# left_revision1_0.net
KiCad netlist of a schematic drawn in EAGLE
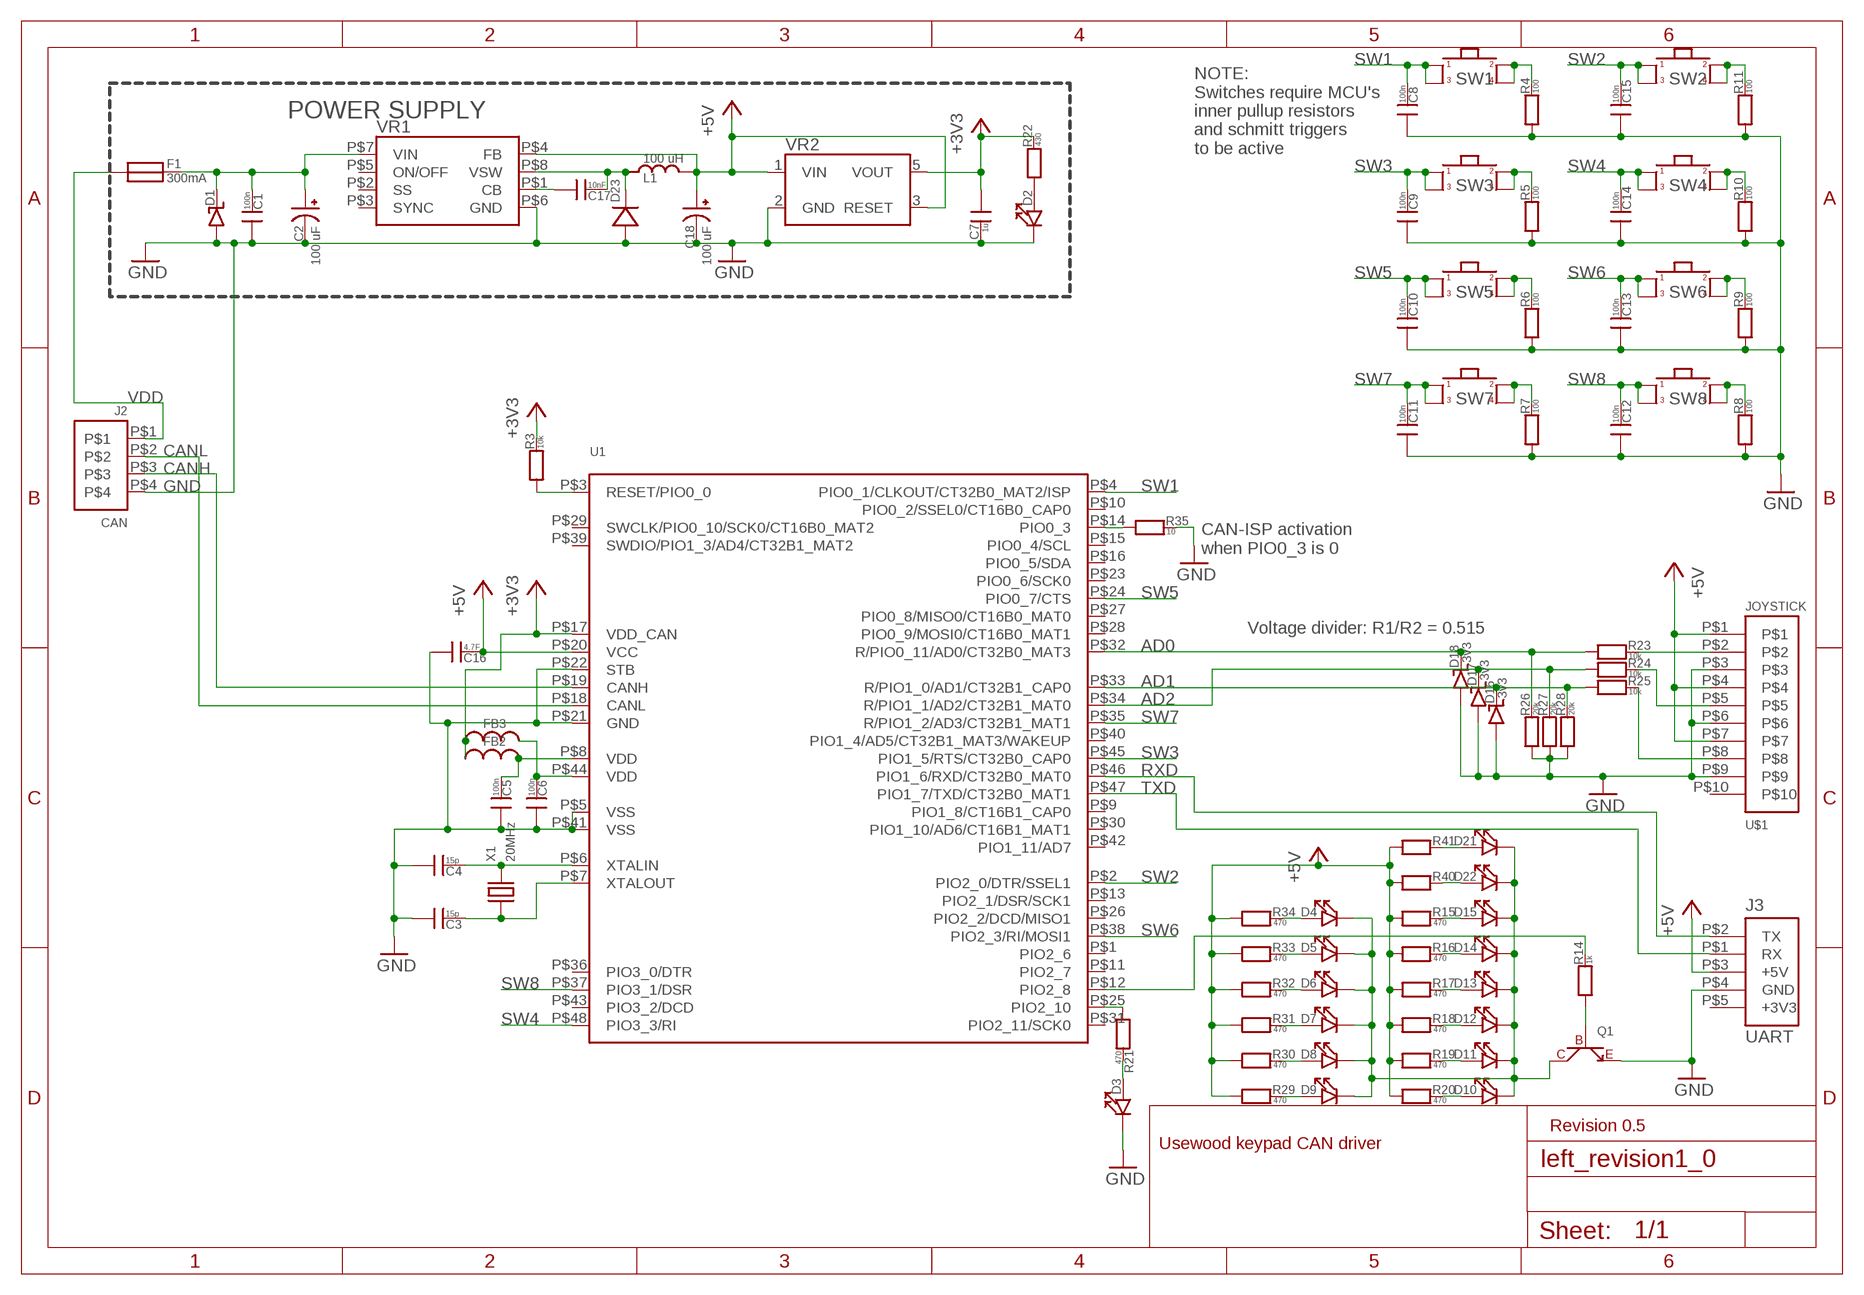
[diagram p0: schematic, sheet 1]

(export (version "E")
  (design (tool "Eeschema 10.0.6"))
  (components
    (comp (ref "C1")
      (value "100n")
      (footprint "eagle-import:0603_SILKSCREEN")
      (libsource (lib "eagle-import") (part "CAP0603_SILKSCREEN"))
    )
    (comp (ref "C2")
      (value "100 uF")
      (footprint "eagle-import:CAP_POL_SMD_10X10X10MM")
      (libsource (lib "eagle-import") (part "CAP_POLSMD_10X10X10MM"))
    )
    (comp (ref "C3")
      (value "15p")
      (footprint "eagle-import:0603_SILKSCREEN")
      (libsource (lib "eagle-import") (part "CAP0603_SILKSCREEN"))
    )
    (comp (ref "C4")
      (value "15p")
      (footprint "eagle-import:0603_SILKSCREEN")
      (libsource (lib "eagle-import") (part "CAP0603_SILKSCREEN"))
    )
    (comp (ref "C5")
      (value "100n")
      (footprint "eagle-import:0603_SILKSCREEN")
      (libsource (lib "eagle-import") (part "CAP0603_SILKSCREEN"))
    )
    (comp (ref "C6")
      (value "100n")
      (footprint "eagle-import:0603_SILKSCREEN")
      (libsource (lib "eagle-import") (part "CAP0603_SILKSCREEN"))
    )
    (comp (ref "C7")
      (value "1u")
      (footprint "eagle-import:0603_SILKSCREEN")
      (libsource (lib "eagle-import") (part "CAP0603_SILKSCREEN"))
    )
    (comp (ref "C8")
      (value "100n")
      (footprint "eagle-import:0603_SILKSCREEN")
      (libsource (lib "eagle-import") (part "CAP0603_SILKSCREEN"))
    )
    (comp (ref "C9")
      (value "100n")
      (footprint "eagle-import:0603_SILKSCREEN")
      (libsource (lib "eagle-import") (part "CAP0603_SILKSCREEN"))
    )
    (comp (ref "C10")
      (value "100n")
      (footprint "eagle-import:0603_SILKSCREEN")
      (libsource (lib "eagle-import") (part "CAP0603_SILKSCREEN"))
    )
    (comp (ref "C11")
      (value "100n")
      (footprint "eagle-import:0603_SILKSCREEN")
      (libsource (lib "eagle-import") (part "CAP0603_SILKSCREEN"))
    )
    (comp (ref "C12")
      (value "100n")
      (footprint "eagle-import:0603_SILKSCREEN")
      (libsource (lib "eagle-import") (part "CAP0603_SILKSCREEN"))
    )
    (comp (ref "C13")
      (value "100n")
      (footprint "eagle-import:0603_SILKSCREEN")
      (libsource (lib "eagle-import") (part "CAP0603_SILKSCREEN"))
    )
    (comp (ref "C14")
      (value "100n")
      (footprint "eagle-import:0603_SILKSCREEN")
      (libsource (lib "eagle-import") (part "CAP0603_SILKSCREEN"))
    )
    (comp (ref "C15")
      (value "100n")
      (footprint "eagle-import:0603_SILKSCREEN")
      (libsource (lib "eagle-import") (part "CAP0603_SILKSCREEN"))
    )
    (comp (ref "C16")
      (value "4.7F")
      (footprint "eagle-import:0603_SILKSCREEN")
      (libsource (lib "eagle-import") (part "CAP0603_SILKSCREEN"))
    )
    (comp (ref "C17")
      (value "10nF")
      (footprint "eagle-import:0603_SILKSCREEN")
      (libsource (lib "eagle-import") (part "CAP0603_SILKSCREEN"))
    )
    (comp (ref "C18")
      (value "100 uF")
      (footprint "eagle-import:CAP_POL_SMD_10X10X10MM")
      (libsource (lib "eagle-import") (part "CAP_POLSMD_10X10X10MM"))
    )
    (comp (ref "D1")
      (value "DIODE_TVSDO-214AA")
      (footprint "eagle-import:DO-214AB")
      (libsource (lib "eagle-import") (part "DIODE_TVSDO-214AA"))
    )
    (comp (ref "D2")
      (value "LED0603_SILKSCREEN")
      (footprint "eagle-import:0603_SILKSCREEN")
      (libsource (lib "eagle-import") (part "LED0603_SILKSCREEN"))
    )
    (comp (ref "D3")
      (value "LED0603_SILKSCREEN")
      (footprint "eagle-import:0603_SILKSCREEN")
      (libsource (lib "eagle-import") (part "LED0603_SILKSCREEN"))
    )
    (comp (ref "D4")
      (value "LED0603_SILKSCREEN")
      (footprint "eagle-import:0603_SILKSCREEN")
      (libsource (lib "eagle-import") (part "LED0603_SILKSCREEN"))
    )
    (comp (ref "D5")
      (value "LED0603_SILKSCREEN")
      (footprint "eagle-import:0603_SILKSCREEN")
      (libsource (lib "eagle-import") (part "LED0603_SILKSCREEN"))
    )
    (comp (ref "D6")
      (value "LED0603_SILKSCREEN")
      (footprint "eagle-import:0603_SILKSCREEN")
      (libsource (lib "eagle-import") (part "LED0603_SILKSCREEN"))
    )
    (comp (ref "D7")
      (value "LED0603_SILKSCREEN")
      (footprint "eagle-import:0603_SILKSCREEN")
      (libsource (lib "eagle-import") (part "LED0603_SILKSCREEN"))
    )
    (comp (ref "D8")
      (value "LED0603_SILKSCREEN")
      (footprint "eagle-import:0603_SILKSCREEN")
      (libsource (lib "eagle-import") (part "LED0603_SILKSCREEN"))
    )
    (comp (ref "D9")
      (value "LED0603_SILKSCREEN")
      (footprint "eagle-import:0603_SILKSCREEN")
      (libsource (lib "eagle-import") (part "LED0603_SILKSCREEN"))
    )
    (comp (ref "D10")
      (value "LED0603_SILKSCREEN")
      (footprint "eagle-import:0603_SILKSCREEN")
      (libsource (lib "eagle-import") (part "LED0603_SILKSCREEN"))
    )
    (comp (ref "D11")
      (value "LED0603_SILKSCREEN")
      (footprint "eagle-import:0603_SILKSCREEN")
      (libsource (lib "eagle-import") (part "LED0603_SILKSCREEN"))
    )
    (comp (ref "D12")
      (value "LED0603_SILKSCREEN")
      (footprint "eagle-import:0603_SILKSCREEN")
      (libsource (lib "eagle-import") (part "LED0603_SILKSCREEN"))
    )
    (comp (ref "D13")
      (value "LED0603_SILKSCREEN")
      (footprint "eagle-import:0603_SILKSCREEN")
      (libsource (lib "eagle-import") (part "LED0603_SILKSCREEN"))
    )
    (comp (ref "D14")
      (value "LED0603_SILKSCREEN")
      (footprint "eagle-import:0603_SILKSCREEN")
      (libsource (lib "eagle-import") (part "LED0603_SILKSCREEN"))
    )
    (comp (ref "D15")
      (value "LED0603_SILKSCREEN")
      (footprint "eagle-import:0603_SILKSCREEN")
      (libsource (lib "eagle-import") (part "LED0603_SILKSCREEN"))
    )
    (comp (ref "D16")
      (value "3v3")
      (footprint "eagle-import:SOD123")
      (libsource (lib "eagle-import") (part "DIODE_ZENERSDO123"))
    )
    (comp (ref "D17")
      (value "3v3")
      (footprint "eagle-import:SOD123")
      (libsource (lib "eagle-import") (part "DIODE_ZENERSDO123"))
    )
    (comp (ref "D18")
      (value "3v3")
      (footprint "eagle-import:SOD123")
      (libsource (lib "eagle-import") (part "DIODE_ZENERSDO123"))
    )
    (comp (ref "D21")
      (value "LED0603_SILKSCREEN")
      (footprint "eagle-import:0603_SILKSCREEN")
      (libsource (lib "eagle-import") (part "LED0603_SILKSCREEN"))
    )
    (comp (ref "D22")
      (value "LED0603_SILKSCREEN")
      (footprint "eagle-import:0603_SILKSCREEN")
      (libsource (lib "eagle-import") (part "LED0603_SILKSCREEN"))
    )
    (comp (ref "D23")
      (value "DIODEDO219AB")
      (footprint "eagle-import:DO219AB")
      (libsource (lib "eagle-import") (part "DIODEDO219AB"))
    )
    (comp (ref "F1")
      (value "300mA")
      (footprint "eagle-import:FUSE_100MA")
      (libsource (lib "eagle-import") (part "FUSE100MA"))
    )
    (comp (ref "FB2")
      (value "FERRITE0603_SILKSCREEN")
      (footprint "eagle-import:0603_SILKSCREEN")
      (libsource (lib "eagle-import") (part "FERRITE0603_SILKSCREEN"))
    )
    (comp (ref "FB3")
      (value "FERRITE0603_SILKSCREEN")
      (footprint "eagle-import:0603_SILKSCREEN")
      (libsource (lib "eagle-import") (part "FERRITE0603_SILKSCREEN"))
    )
    (comp (ref "J2")
      (value "CAN")
      (footprint "eagle-import:MOLEX_MICRO-FIT_4WAY")
      (libsource (lib "eagle-import") (part "MOLEX_MICRO-FIT_4WAYTH"))
    )
    (comp (ref "J3")
      (value "UART")
      (footprint "eagle-import:HEADER5_1")
      (libsource (lib "eagle-import") (part "HEADER_USARTTH"))
    )
    (comp (ref "L1")
      (value "100 uH")
      (footprint "eagle-import:INDUCTOR_BOURNS_10X13X5MM")
      (libsource (lib "eagle-import") (part "INDUCTORBOURNS_10X13X5MM"))
    )
    (comp (ref "Q1")
      (value "NPN_TRANSISTORSOT323")
      (footprint "eagle-import:SOT323")
      (libsource (lib "eagle-import") (part "NPN_TRANSISTORSOT323"))
    )
    (comp (ref "R3")
      (value "10k")
      (footprint "eagle-import:0603_SILKSCREEN")
      (libsource (lib "eagle-import") (part "RES0604_SILKSCREEN"))
    )
    (comp (ref "R4")
      (value "100")
      (footprint "eagle-import:0603_SILKSCREEN")
      (libsource (lib "eagle-import") (part "RES0604_SILKSCREEN"))
    )
    (comp (ref "R5")
      (value "100")
      (footprint "eagle-import:0603_SILKSCREEN")
      (libsource (lib "eagle-import") (part "RES0604_SILKSCREEN"))
    )
    (comp (ref "R6")
      (value "100")
      (footprint "eagle-import:0603_SILKSCREEN")
      (libsource (lib "eagle-import") (part "RES0604_SILKSCREEN"))
    )
    (comp (ref "R7")
      (value "100")
      (footprint "eagle-import:0603_SILKSCREEN")
      (libsource (lib "eagle-import") (part "RES0604_SILKSCREEN"))
    )
    (comp (ref "R8")
      (value "100")
      (footprint "eagle-import:0603_SILKSCREEN")
      (libsource (lib "eagle-import") (part "RES0604_SILKSCREEN"))
    )
    (comp (ref "R9")
      (value "100")
      (footprint "eagle-import:0603_SILKSCREEN")
      (libsource (lib "eagle-import") (part "RES0604_SILKSCREEN"))
    )
    (comp (ref "R10")
      (value "100")
      (footprint "eagle-import:0603_SILKSCREEN")
      (libsource (lib "eagle-import") (part "RES0604_SILKSCREEN"))
    )
    (comp (ref "R11")
      (value "100")
      (footprint "eagle-import:0603_SILKSCREEN")
      (libsource (lib "eagle-import") (part "RES0604_SILKSCREEN"))
    )
    (comp (ref "R14")
      (value "1k")
      (footprint "eagle-import:0603_SILKSCREEN")
      (libsource (lib "eagle-import") (part "RES0604_SILKSCREEN"))
    )
    (comp (ref "R15")
      (value "470")
      (footprint "eagle-import:0603_SILKSCREEN")
      (libsource (lib "eagle-import") (part "RES0604_SILKSCREEN"))
    )
    (comp (ref "R16")
      (value "470")
      (footprint "eagle-import:0603_SILKSCREEN")
      (libsource (lib "eagle-import") (part "RES0604_SILKSCREEN"))
    )
    (comp (ref "R17")
      (value "470")
      (footprint "eagle-import:0603_SILKSCREEN")
      (libsource (lib "eagle-import") (part "RES0604_SILKSCREEN"))
    )
    (comp (ref "R18")
      (value "470")
      (footprint "eagle-import:0603_SILKSCREEN")
      (libsource (lib "eagle-import") (part "RES0604_SILKSCREEN"))
    )
    (comp (ref "R19")
      (value "470")
      (footprint "eagle-import:0603_SILKSCREEN")
      (libsource (lib "eagle-import") (part "RES0604_SILKSCREEN"))
    )
    (comp (ref "R20")
      (value "470")
      (footprint "eagle-import:0603_SILKSCREEN")
      (libsource (lib "eagle-import") (part "RES0604_SILKSCREEN"))
    )
    (comp (ref "R21")
      (value "470")
      (footprint "eagle-import:0603_SILKSCREEN")
      (libsource (lib "eagle-import") (part "RES0604_SILKSCREEN"))
    )
    (comp (ref "R22")
      (value "430")
      (footprint "eagle-import:0603_SILKSCREEN")
      (libsource (lib "eagle-import") (part "RES0604_SILKSCREEN"))
    )
    (comp (ref "R23")
      (value "10k")
      (footprint "eagle-import:0603_SILKSCREEN")
      (libsource (lib "eagle-import") (part "RES0604_SILKSCREEN"))
    )
    (comp (ref "R24")
      (value "10k")
      (footprint "eagle-import:0603_SILKSCREEN")
      (libsource (lib "eagle-import") (part "RES0604_SILKSCREEN"))
    )
    (comp (ref "R25")
      (value "10k")
      (footprint "eagle-import:0603_SILKSCREEN")
      (libsource (lib "eagle-import") (part "RES0604_SILKSCREEN"))
    )
    (comp (ref "R26")
      (value "20k")
      (footprint "eagle-import:0603_SILKSCREEN")
      (libsource (lib "eagle-import") (part "RES0604_SILKSCREEN"))
    )
    (comp (ref "R27")
      (value "20k")
      (footprint "eagle-import:0603_SILKSCREEN")
      (libsource (lib "eagle-import") (part "RES0604_SILKSCREEN"))
    )
    (comp (ref "R28")
      (value "20k")
      (footprint "eagle-import:0603_SILKSCREEN")
      (libsource (lib "eagle-import") (part "RES0604_SILKSCREEN"))
    )
    (comp (ref "R29")
      (value "470")
      (footprint "eagle-import:0603_SILKSCREEN")
      (libsource (lib "eagle-import") (part "RES0604_SILKSCREEN"))
    )
    (comp (ref "R30")
      (value "470")
      (footprint "eagle-import:0603_SILKSCREEN")
      (libsource (lib "eagle-import") (part "RES0604_SILKSCREEN"))
    )
    (comp (ref "R31")
      (value "470")
      (footprint "eagle-import:0603_SILKSCREEN")
      (libsource (lib "eagle-import") (part "RES0604_SILKSCREEN"))
    )
    (comp (ref "R32")
      (value "470")
      (footprint "eagle-import:0603_SILKSCREEN")
      (libsource (lib "eagle-import") (part "RES0604_SILKSCREEN"))
    )
    (comp (ref "R33")
      (value "470")
      (footprint "eagle-import:0603_SILKSCREEN")
      (libsource (lib "eagle-import") (part "RES0604_SILKSCREEN"))
    )
    (comp (ref "R34")
      (value "470")
      (footprint "eagle-import:0603_SILKSCREEN")
      (libsource (lib "eagle-import") (part "RES0604_SILKSCREEN"))
    )
    (comp (ref "R35")
      (value "10")
      (footprint "eagle-import:0603_SILKSCREEN")
      (libsource (lib "eagle-import") (part "RES0604_SILKSCREEN"))
    )
    (comp (ref "R40")
      (value "RES0604_SILKSCREEN")
      (footprint "eagle-import:0603_SILKSCREEN")
      (libsource (lib "eagle-import") (part "RES0604_SILKSCREEN"))
    )
    (comp (ref "R41")
      (value "RES0604_SILKSCREEN")
      (footprint "eagle-import:0603_SILKSCREEN")
      (libsource (lib "eagle-import") (part "RES0604_SILKSCREEN"))
    )
    (comp (ref "SW1")
      (value "SWITCH12X12MM_CENTER_HOLE")
      (footprint "eagle-import:SWITCH_12X12MM_CENTER_HOLE")
      (libsource (lib "eagle-import") (part "SWITCH12X12MM_CENTER_HOLE"))
    )
    (comp (ref "SW2")
      (value "SWITCH12X12MM_CENTER_HOLE")
      (footprint "eagle-import:SWITCH_12X12MM_CENTER_HOLE")
      (libsource (lib "eagle-import") (part "SWITCH12X12MM_CENTER_HOLE"))
    )
    (comp (ref "SW3")
      (value "SWITCH12X12MM_CENTER_HOLE")
      (footprint "eagle-import:SWITCH_12X12MM_CENTER_HOLE")
      (libsource (lib "eagle-import") (part "SWITCH12X12MM_CENTER_HOLE"))
    )
    (comp (ref "SW4")
      (value "SWITCH12X12MM_CENTER_HOLE")
      (footprint "eagle-import:SWITCH_12X12MM_CENTER_HOLE")
      (libsource (lib "eagle-import") (part "SWITCH12X12MM_CENTER_HOLE"))
    )
    (comp (ref "SW5")
      (value "SWITCH12X12MM_CENTER_HOLE")
      (footprint "eagle-import:SWITCH_12X12MM_CENTER_HOLE")
      (libsource (lib "eagle-import") (part "SWITCH12X12MM_CENTER_HOLE"))
    )
    (comp (ref "SW6")
      (value "SWITCH12X12MM_CENTER_HOLE")
      (footprint "eagle-import:SWITCH_12X12MM_CENTER_HOLE")
      (libsource (lib "eagle-import") (part "SWITCH12X12MM_CENTER_HOLE"))
    )
    (comp (ref "SW7")
      (value "SWITCH12X12MM_CENTER_HOLE")
      (footprint "eagle-import:SWITCH_12X12MM_CENTER_HOLE")
      (libsource (lib "eagle-import") (part "SWITCH12X12MM_CENTER_HOLE"))
    )
    (comp (ref "SW8")
      (value "SWITCH12X12MM_CENTER_HOLE")
      (footprint "eagle-import:SWITCH_12X12MM_CENTER_HOLE")
      (libsource (lib "eagle-import") (part "SWITCH12X12MM_CENTER_HOLE"))
    )
    (comp (ref "U$1")
      (value "JOYSTICK")
      (footprint "eagle-import:MOLEX-MICRO-FIT_10WAY")
      (libsource (lib "eagle-import") (part "MOLEX_MICRO-FIT_10WAYTH"))
    )
    (comp (ref "U1")
      (value "LPC11C22QFP48")
      (footprint "eagle-import:QFP48")
      (libsource (lib "eagle-import") (part "LPC11C22QFP48"))
    )
    (comp (ref "VR1")
      (value "LM2671SOIC8")
      (footprint "eagle-import:SOIC8")
      (libsource (lib "eagle-import") (part "LM2671SOIC8"))
    )
    (comp (ref "VR2")
      (value "LP2985SOP5")
      (footprint "eagle-import:SOP5")
      (libsource (lib "eagle-import") (part "LP2985SOP5"))
    )
    (comp (ref "X1")
      (value "20MHz")
      (footprint "eagle-import:XTAL_SMD_5X3.2")
      (libsource (lib "eagle-import") (part "XTALSMD_5X3.2"))
    )
  )
  (nets
    (net (code "1") (name "+3V3") (class "Default")
      (node (ref "C7") (pin "0") (pinfunction "P$1_0") (pintype "bidirectional"))
      (node (ref "FB2") (pin "0") (pinfunction "P$1_0") (pintype "bidirectional"))
      (node (ref "FB3") (pin "0") (pinfunction "P$1_0") (pintype "bidirectional"))
      (node (ref "R22") (pin "1") (pinfunction "P$2_1") (pintype "bidirectional"))
      (node (ref "R3") (pin "1") (pinfunction "P$2_1") (pintype "bidirectional"))
      (node (ref "U1") (pin "P$17") (pinfunction "VDD_CAN_P$17") (pintype "bidirectional"))
      (node (ref "VR2") (pin "5") (pinfunction "VOUT_5") (pintype "bidirectional"))
    )
    (net (code "2") (name "+5V") (class "Default")
      (node (ref "C16") (pin "1") (pinfunction "P$2_1") (pintype "bidirectional"))
      (node (ref "C18") (pin "+") (pinfunction "+_+") (pintype "bidirectional"))
      (node (ref "J3") (pin "P$3") (pinfunction "+5V_P$3") (pintype "bidirectional"))
      (node (ref "L1") (pin "P$2") (pinfunction "P$2_P$2") (pintype "bidirectional"))
      (node (ref "R15") (pin "0") (pinfunction "P$1_0") (pintype "bidirectional"))
      (node (ref "R16") (pin "0") (pinfunction "P$1_0") (pintype "bidirectional"))
      (node (ref "R17") (pin "0") (pinfunction "P$1_0") (pintype "bidirectional"))
      (node (ref "R18") (pin "0") (pinfunction "P$1_0") (pintype "bidirectional"))
      (node (ref "R19") (pin "0") (pinfunction "P$1_0") (pintype "bidirectional"))
      (node (ref "R20") (pin "0") (pinfunction "P$1_0") (pintype "bidirectional"))
      (node (ref "R29") (pin "0") (pinfunction "P$1_0") (pintype "bidirectional"))
      (node (ref "R30") (pin "0") (pinfunction "P$1_0") (pintype "bidirectional"))
      (node (ref "R31") (pin "0") (pinfunction "P$1_0") (pintype "bidirectional"))
      (node (ref "R32") (pin "0") (pinfunction "P$1_0") (pintype "bidirectional"))
      (node (ref "R33") (pin "0") (pinfunction "P$1_0") (pintype "bidirectional"))
      (node (ref "R34") (pin "0") (pinfunction "P$1_0") (pintype "bidirectional"))
      (node (ref "R40") (pin "0") (pinfunction "P$1_0") (pintype "bidirectional"))
      (node (ref "R41") (pin "0") (pinfunction "P$1_0") (pintype "bidirectional"))
      (node (ref "U$1") (pin "P$1") (pinfunction "P$1_P$1") (pintype "bidirectional"))
      (node (ref "U$1") (pin "P$4") (pinfunction "P$4_P$4") (pintype "bidirectional"))
      (node (ref "U$1") (pin "P$7") (pinfunction "P$7_P$7") (pintype "bidirectional"))
      (node (ref "U1") (pin "P$20") (pinfunction "VCC_P$20") (pintype "bidirectional"))
      (node (ref "VR1") (pin "P$4") (pinfunction "FB_P$4") (pintype "bidirectional"))
      (node (ref "VR2") (pin "1") (pinfunction "VIN_1") (pintype "bidirectional"))
      (node (ref "VR2") (pin "3") (pinfunction "RESET_3") (pintype "bidirectional"))
    )
    (net (code "3") (name "/AD0") (class "Default")
      (node (ref "D18") (pin "P$2") (pinfunction "N_P$2") (pintype "bidirectional"))
      (node (ref "R23") (pin "0") (pinfunction "P$1_0") (pintype "bidirectional"))
      (node (ref "R26") (pin "1") (pinfunction "P$2_1") (pintype "bidirectional"))
      (node (ref "U1") (pin "P$32") (pinfunction "R/PIO0_11/AD0/CT32B0_MAT3_P$32") (pintype "bidirectional"))
    )
    (net (code "4") (name "/AD1") (class "Default")
      (node (ref "D16") (pin "P$2") (pinfunction "N_P$2") (pintype "bidirectional"))
      (node (ref "R25") (pin "0") (pinfunction "P$1_0") (pintype "bidirectional"))
      (node (ref "R28") (pin "1") (pinfunction "P$2_1") (pintype "bidirectional"))
      (node (ref "U1") (pin "P$33") (pinfunction "R/PIO1_0/AD1/CT32B1_CAP0_P$33") (pintype "bidirectional"))
    )
    (net (code "5") (name "/AD2") (class "Default")
      (node (ref "D17") (pin "P$2") (pinfunction "N_P$2") (pintype "bidirectional"))
      (node (ref "R24") (pin "0") (pinfunction "P$1_0") (pintype "bidirectional"))
      (node (ref "R27") (pin "1") (pinfunction "P$2_1") (pintype "bidirectional"))
      (node (ref "U1") (pin "P$34") (pinfunction "R/PIO1_1/AD2/CT32B1_MAT0_P$34") (pintype "bidirectional"))
    )
    (net (code "6") (name "/CANH") (class "Default")
      (node (ref "J2") (pin "P$3") (pinfunction "P$3_P$3") (pintype "bidirectional"))
      (node (ref "U1") (pin "P$19") (pinfunction "CANH_P$19") (pintype "bidirectional"))
    )
    (net (code "7") (name "/CANL") (class "Default")
      (node (ref "J2") (pin "P$2") (pinfunction "P$2_P$2") (pintype "bidirectional"))
      (node (ref "U1") (pin "P$18") (pinfunction "CANL_P$18") (pintype "bidirectional"))
    )
    (net (code "8") (name "/RXD") (class "Default")
      (node (ref "J3") (pin "P$2") (pinfunction "TX_P$2") (pintype "bidirectional"))
      (node (ref "U1") (pin "P$46") (pinfunction "PIO1_6/RXD/CT32B0_MAT0_P$46") (pintype "bidirectional"))
    )
    (net (code "9") (name "/SW1") (class "Default")
      (node (ref "C8") (pin "1") (pinfunction "P$2_1") (pintype "bidirectional"))
      (node (ref "SW1") (pin "P$1") (pinfunction "P$1_P$1") (pintype "bidirectional"))
      (node (ref "SW1") (pin "P$2") (pinfunction "P$3_P$2") (pintype "bidirectional"))
      (node (ref "U1") (pin "P$4") (pinfunction "PIO0_1/CLKOUT/CT32B0_MAT2/ISP_P$4") (pintype "bidirectional"))
    )
    (net (code "10") (name "/SW2") (class "Default")
      (node (ref "C15") (pin "1") (pinfunction "P$2_1") (pintype "bidirectional"))
      (node (ref "SW2") (pin "P$1") (pinfunction "P$1_P$1") (pintype "bidirectional"))
      (node (ref "SW2") (pin "P$2") (pinfunction "P$3_P$2") (pintype "bidirectional"))
      (node (ref "U1") (pin "P$2") (pinfunction "PIO2_0/DTR/SSEL1_P$2") (pintype "bidirectional"))
    )
    (net (code "11") (name "/SW3") (class "Default")
      (node (ref "C9") (pin "1") (pinfunction "P$2_1") (pintype "bidirectional"))
      (node (ref "SW3") (pin "P$1") (pinfunction "P$1_P$1") (pintype "bidirectional"))
      (node (ref "SW3") (pin "P$2") (pinfunction "P$3_P$2") (pintype "bidirectional"))
      (node (ref "U1") (pin "P$45") (pinfunction "PIO1_5/RTS/CT32B0_CAP0_P$45") (pintype "bidirectional"))
    )
    (net (code "12") (name "/SW4") (class "Default")
      (node (ref "C14") (pin "1") (pinfunction "P$2_1") (pintype "bidirectional"))
      (node (ref "SW4") (pin "P$1") (pinfunction "P$1_P$1") (pintype "bidirectional"))
      (node (ref "SW4") (pin "P$2") (pinfunction "P$3_P$2") (pintype "bidirectional"))
      (node (ref "U1") (pin "P$48") (pinfunction "PIO3_3/RI_P$48") (pintype "bidirectional"))
    )
    (net (code "13") (name "/SW5") (class "Default")
      (node (ref "C10") (pin "1") (pinfunction "P$2_1") (pintype "bidirectional"))
      (node (ref "SW5") (pin "P$1") (pinfunction "P$1_P$1") (pintype "bidirectional"))
      (node (ref "SW5") (pin "P$2") (pinfunction "P$3_P$2") (pintype "bidirectional"))
      (node (ref "U1") (pin "P$24") (pinfunction "PIO0_7/CTS_P$24") (pintype "bidirectional"))
    )
    (net (code "14") (name "/SW6") (class "Default")
      (node (ref "C13") (pin "1") (pinfunction "P$2_1") (pintype "bidirectional"))
      (node (ref "SW6") (pin "P$1") (pinfunction "P$1_P$1") (pintype "bidirectional"))
      (node (ref "SW6") (pin "P$2") (pinfunction "P$3_P$2") (pintype "bidirectional"))
      (node (ref "U1") (pin "P$38") (pinfunction "PIO2_3/RI/MOSI1_P$38") (pintype "bidirectional"))
    )
    (net (code "15") (name "/SW7") (class "Default")
      (node (ref "C11") (pin "1") (pinfunction "P$2_1") (pintype "bidirectional"))
      (node (ref "SW7") (pin "P$1") (pinfunction "P$1_P$1") (pintype "bidirectional"))
      (node (ref "SW7") (pin "P$2") (pinfunction "P$3_P$2") (pintype "bidirectional"))
      (node (ref "U1") (pin "P$35") (pinfunction "R/PIO1_2/AD3/CT32B1_MAT1_P$35") (pintype "bidirectional"))
    )
    (net (code "16") (name "/SW8") (class "Default")
      (node (ref "C12") (pin "1") (pinfunction "P$2_1") (pintype "bidirectional"))
      (node (ref "SW8") (pin "P$1") (pinfunction "P$1_P$1") (pintype "bidirectional"))
      (node (ref "SW8") (pin "P$2") (pinfunction "P$3_P$2") (pintype "bidirectional"))
      (node (ref "U1") (pin "P$37") (pinfunction "PIO3_1/DSR_P$37") (pintype "bidirectional"))
    )
    (net (code "17") (name "/TXD") (class "Default")
      (node (ref "J3") (pin "P$1") (pinfunction "RX_P$1") (pintype "bidirectional"))
      (node (ref "U1") (pin "P$47") (pinfunction "PIO1_7/TXD/CT32B0_MAT1_P$47") (pintype "bidirectional"))
    )
    (net (code "18") (name "/VDD") (class "Default")
      (node (ref "F1") (pin "P$1") (pinfunction "P$1_P$1") (pintype "bidirectional"))
      (node (ref "J2") (pin "P$1") (pinfunction "P$1_P$1") (pintype "bidirectional"))
    )
    (net (code "19") (name "GND") (class "Default")
      (node (ref "C1") (pin "0") (pinfunction "P$1_0") (pintype "bidirectional"))
      (node (ref "C10") (pin "0") (pinfunction "P$1_0") (pintype "bidirectional"))
      (node (ref "C11") (pin "0") (pinfunction "P$1_0") (pintype "bidirectional"))
      (node (ref "C12") (pin "0") (pinfunction "P$1_0") (pintype "bidirectional"))
      (node (ref "C13") (pin "0") (pinfunction "P$1_0") (pintype "bidirectional"))
      (node (ref "C14") (pin "0") (pinfunction "P$1_0") (pintype "bidirectional"))
      (node (ref "C15") (pin "0") (pinfunction "P$1_0") (pintype "bidirectional"))
      (node (ref "C16") (pin "0") (pinfunction "P$1_0") (pintype "bidirectional"))
      (node (ref "C18") (pin "-") (pinfunction "-_-") (pintype "bidirectional"))
      (node (ref "C2") (pin "-") (pinfunction "-_-") (pintype "bidirectional"))
      (node (ref "C3") (pin "0") (pinfunction "P$1_0") (pintype "bidirectional"))
      (node (ref "C4") (pin "0") (pinfunction "P$1_0") (pintype "bidirectional"))
      (node (ref "C5") (pin "0") (pinfunction "P$1_0") (pintype "bidirectional"))
      (node (ref "C6") (pin "0") (pinfunction "P$1_0") (pintype "bidirectional"))
      (node (ref "C7") (pin "1") (pinfunction "P$2_1") (pintype "bidirectional"))
      (node (ref "C8") (pin "0") (pinfunction "P$1_0") (pintype "bidirectional"))
      (node (ref "C9") (pin "0") (pinfunction "P$1_0") (pintype "bidirectional"))
      (node (ref "D1") (pin "P$1") (pinfunction "P_P$1") (pintype "bidirectional"))
      (node (ref "D16") (pin "P$1") (pinfunction "P_P$1") (pintype "bidirectional"))
      (node (ref "D17") (pin "P$1") (pinfunction "P_P$1") (pintype "bidirectional"))
      (node (ref "D18") (pin "P$1") (pinfunction "P_P$1") (pintype "bidirectional"))
      (node (ref "D2") (pin "1") (pinfunction "1_1") (pintype "bidirectional"))
      (node (ref "D23") (pin "P$1") (pinfunction "P_P$1") (pintype "bidirectional"))
      (node (ref "D3") (pin "1") (pinfunction "1_1") (pintype "bidirectional"))
      (node (ref "J2") (pin "P$4") (pinfunction "P$4_P$4") (pintype "bidirectional"))
      (node (ref "J3") (pin "P$4") (pinfunction "GND_P$4") (pintype "bidirectional"))
      (node (ref "Q1") (pin "R") (pinfunction "E_R") (pintype "bidirectional"))
      (node (ref "R10") (pin "0") (pinfunction "P$1_0") (pintype "bidirectional"))
      (node (ref "R11") (pin "0") (pinfunction "P$1_0") (pintype "bidirectional"))
      (node (ref "R26") (pin "0") (pinfunction "P$1_0") (pintype "bidirectional"))
      (node (ref "R27") (pin "0") (pinfunction "P$1_0") (pintype "bidirectional"))
      (node (ref "R28") (pin "0") (pinfunction "P$1_0") (pintype "bidirectional"))
      (node (ref "R35") (pin "1") (pinfunction "P$2_1") (pintype "bidirectional"))
      (node (ref "R4") (pin "0") (pinfunction "P$1_0") (pintype "bidirectional"))
      (node (ref "R5") (pin "0") (pinfunction "P$1_0") (pintype "bidirectional"))
      (node (ref "R6") (pin "0") (pinfunction "P$1_0") (pintype "bidirectional"))
      (node (ref "R7") (pin "0") (pinfunction "P$1_0") (pintype "bidirectional"))
      (node (ref "R8") (pin "0") (pinfunction "P$1_0") (pintype "bidirectional"))
      (node (ref "R9") (pin "0") (pinfunction "P$1_0") (pintype "bidirectional"))
      (node (ref "U$1") (pin "P$3") (pinfunction "P$3_P$3") (pintype "bidirectional"))
      (node (ref "U$1") (pin "P$6") (pinfunction "P$6_P$6") (pintype "bidirectional"))
      (node (ref "U$1") (pin "P$9") (pinfunction "P$9_P$9") (pintype "bidirectional"))
      (node (ref "U1") (pin "P$21") (pinfunction "GND_P$21") (pintype "bidirectional"))
      (node (ref "U1") (pin "P$22") (pinfunction "STB_P$22") (pintype "bidirectional"))
      (node (ref "U1") (pin "P$41") (pinfunction "VSS_P$41") (pintype "bidirectional"))
      (node (ref "U1") (pin "P$5") (pinfunction "VSS_P$5") (pintype "bidirectional"))
      (node (ref "VR1") (pin "P$6") (pinfunction "GND_P$6") (pintype "bidirectional"))
      (node (ref "VR2") (pin "2") (pinfunction "GND_2") (pintype "bidirectional"))
    )
    (net (code "20") (name "Net-(C1-P$2)") (class "Default")
      (node (ref "C1") (pin "1") (pinfunction "P$2_1") (pintype "bidirectional"))
      (node (ref "C2") (pin "+") (pinfunction "+_+") (pintype "bidirectional"))
      (node (ref "D1") (pin "P$2") (pinfunction "N_P$2") (pintype "bidirectional"))
      (node (ref "F1") (pin "P$2") (pinfunction "P$2_P$2") (pintype "bidirectional"))
      (node (ref "VR1") (pin "P$7") (pinfunction "VIN_P$7") (pintype "bidirectional"))
    )
    (net (code "21") (name "Net-(C3-P$2)") (class "Default")
      (node (ref "C3") (pin "1") (pinfunction "P$2_1") (pintype "bidirectional"))
      (node (ref "U1") (pin "P$7") (pinfunction "XTALOUT_P$7") (pintype "bidirectional"))
      (node (ref "X1") (pin "P$1") (pinfunction "P$1_P$1") (pintype "bidirectional"))
    )
    (net (code "22") (name "Net-(C4-P$2)") (class "Default")
      (node (ref "C4") (pin "1") (pinfunction "P$2_1") (pintype "bidirectional"))
      (node (ref "U1") (pin "P$6") (pinfunction "XTALIN_P$6") (pintype "bidirectional"))
      (node (ref "X1") (pin "P$2") (pinfunction "P$2_P$2") (pintype "bidirectional"))
    )
    (net (code "23") (name "Net-(C5-P$2)") (class "Default")
      (node (ref "C5") (pin "1") (pinfunction "P$2_1") (pintype "bidirectional"))
      (node (ref "FB2") (pin "1") (pinfunction "P$2_1") (pintype "bidirectional"))
      (node (ref "U1") (pin "P$8") (pinfunction "VDD_P$8") (pintype "bidirectional"))
    )
    (net (code "24") (name "Net-(C6-P$2)") (class "Default")
      (node (ref "C6") (pin "1") (pinfunction "P$2_1") (pintype "bidirectional"))
      (node (ref "FB3") (pin "1") (pinfunction "P$2_1") (pintype "bidirectional"))
      (node (ref "U1") (pin "P$44") (pinfunction "VDD_P$44") (pintype "bidirectional"))
    )
    (net (code "25") (name "Net-(C17-P$1)") (class "Default")
      (node (ref "C17") (pin "0") (pinfunction "P$1_0") (pintype "bidirectional"))
      (node (ref "VR1") (pin "P$1") (pinfunction "CB_P$1") (pintype "bidirectional"))
    )
    (net (code "26") (name "Net-(C17-P$2)") (class "Default")
      (node (ref "C17") (pin "1") (pinfunction "P$2_1") (pintype "bidirectional"))
      (node (ref "D23") (pin "P$2") (pinfunction "N_P$2") (pintype "bidirectional"))
      (node (ref "L1") (pin "P$1") (pinfunction "P$1_P$1") (pintype "bidirectional"))
      (node (ref "VR1") (pin "P$8") (pinfunction "VSW_P$8") (pintype "bidirectional"))
    )
    (net (code "27") (name "Net-(Q1-B)") (class "Default")
      (node (ref "Q1") (pin "L") (pinfunction "B_L") (pintype "bidirectional"))
      (node (ref "R14") (pin "0") (pinfunction "P$1_0") (pintype "bidirectional"))
    )
    (net (code "28") (name "Net-(Q1-C)") (class "Default")
      (node (ref "D10") (pin "1") (pinfunction "1_1") (pintype "bidirectional"))
      (node (ref "D11") (pin "1") (pinfunction "1_1") (pintype "bidirectional"))
      (node (ref "D12") (pin "1") (pinfunction "1_1") (pintype "bidirectional"))
      (node (ref "D13") (pin "1") (pinfunction "1_1") (pintype "bidirectional"))
      (node (ref "D14") (pin "1") (pinfunction "1_1") (pintype "bidirectional"))
      (node (ref "D15") (pin "1") (pinfunction "1_1") (pintype "bidirectional"))
      (node (ref "D21") (pin "1") (pinfunction "1_1") (pintype "bidirectional"))
      (node (ref "D22") (pin "1") (pinfunction "1_1") (pintype "bidirectional"))
      (node (ref "D4") (pin "1") (pinfunction "1_1") (pintype "bidirectional"))
      (node (ref "D5") (pin "1") (pinfunction "1_1") (pintype "bidirectional"))
      (node (ref "D6") (pin "1") (pinfunction "1_1") (pintype "bidirectional"))
      (node (ref "D7") (pin "1") (pinfunction "1_1") (pintype "bidirectional"))
      (node (ref "D8") (pin "1") (pinfunction "1_1") (pintype "bidirectional"))
      (node (ref "D9") (pin "1") (pinfunction "1_1") (pintype "bidirectional"))
      (node (ref "Q1") (pin "M") (pinfunction "C_M") (pintype "bidirectional"))
    )
    (net (code "29") (name "Net-(R3-P$1)") (class "Default")
      (node (ref "R3") (pin "0") (pinfunction "P$1_0") (pintype "bidirectional"))
      (node (ref "U1") (pin "P$3") (pinfunction "RESET/PIO0_0_P$3") (pintype "bidirectional"))
    )
    (net (code "30") (name "Net-(R4-P$2)") (class "Default")
      (node (ref "R4") (pin "1") (pinfunction "P$2_1") (pintype "bidirectional"))
      (node (ref "SW1") (pin "P$3") (pinfunction "P$2_P$3") (pintype "bidirectional"))
      (node (ref "SW1") (pin "P$4") (pinfunction "P$4_P$4") (pintype "bidirectional"))
    )
    (net (code "31") (name "Net-(R5-P$2)") (class "Default")
      (node (ref "R5") (pin "1") (pinfunction "P$2_1") (pintype "bidirectional"))
      (node (ref "SW3") (pin "P$3") (pinfunction "P$2_P$3") (pintype "bidirectional"))
      (node (ref "SW3") (pin "P$4") (pinfunction "P$4_P$4") (pintype "bidirectional"))
    )
    (net (code "32") (name "Net-(R6-P$2)") (class "Default")
      (node (ref "R6") (pin "1") (pinfunction "P$2_1") (pintype "bidirectional"))
      (node (ref "SW5") (pin "P$3") (pinfunction "P$2_P$3") (pintype "bidirectional"))
      (node (ref "SW5") (pin "P$4") (pinfunction "P$4_P$4") (pintype "bidirectional"))
    )
    (net (code "33") (name "Net-(R7-P$2)") (class "Default")
      (node (ref "R7") (pin "1") (pinfunction "P$2_1") (pintype "bidirectional"))
      (node (ref "SW7") (pin "P$3") (pinfunction "P$2_P$3") (pintype "bidirectional"))
      (node (ref "SW7") (pin "P$4") (pinfunction "P$4_P$4") (pintype "bidirectional"))
    )
    (net (code "34") (name "Net-(R8-P$2)") (class "Default")
      (node (ref "R8") (pin "1") (pinfunction "P$2_1") (pintype "bidirectional"))
      (node (ref "SW8") (pin "P$3") (pinfunction "P$2_P$3") (pintype "bidirectional"))
      (node (ref "SW8") (pin "P$4") (pinfunction "P$4_P$4") (pintype "bidirectional"))
    )
    (net (code "35") (name "Net-(R9-P$2)") (class "Default")
      (node (ref "R9") (pin "1") (pinfunction "P$2_1") (pintype "bidirectional"))
      (node (ref "SW6") (pin "P$3") (pinfunction "P$2_P$3") (pintype "bidirectional"))
      (node (ref "SW6") (pin "P$4") (pinfunction "P$4_P$4") (pintype "bidirectional"))
    )
    (net (code "36") (name "Net-(R10-P$2)") (class "Default")
      (node (ref "R10") (pin "1") (pinfunction "P$2_1") (pintype "bidirectional"))
      (node (ref "SW4") (pin "P$3") (pinfunction "P$2_P$3") (pintype "bidirectional"))
      (node (ref "SW4") (pin "P$4") (pinfunction "P$4_P$4") (pintype "bidirectional"))
    )
    (net (code "37") (name "Net-(R11-P$2)") (class "Default")
      (node (ref "R11") (pin "1") (pinfunction "P$2_1") (pintype "bidirectional"))
      (node (ref "SW2") (pin "P$3") (pinfunction "P$2_P$3") (pintype "bidirectional"))
      (node (ref "SW2") (pin "P$4") (pinfunction "P$4_P$4") (pintype "bidirectional"))
    )
    (net (code "38") (name "Net-(R14-P$2)") (class "Default")
      (node (ref "R14") (pin "1") (pinfunction "P$2_1") (pintype "bidirectional"))
      (node (ref "U1") (pin "P$12") (pinfunction "PIO2_8_P$12") (pintype "bidirectional"))
    )
    (net (code "39") (name "Net-(R15-P$2)") (class "Default")
      (node (ref "D15") (pin "0") (pinfunction "0_0") (pintype "bidirectional"))
      (node (ref "R15") (pin "1") (pinfunction "P$2_1") (pintype "bidirectional"))
    )
    (net (code "40") (name "Net-(R16-P$2)") (class "Default")
      (node (ref "D14") (pin "0") (pinfunction "0_0") (pintype "bidirectional"))
      (node (ref "R16") (pin "1") (pinfunction "P$2_1") (pintype "bidirectional"))
    )
    (net (code "41") (name "Net-(R17-P$2)") (class "Default")
      (node (ref "D13") (pin "0") (pinfunction "0_0") (pintype "bidirectional"))
      (node (ref "R17") (pin "1") (pinfunction "P$2_1") (pintype "bidirectional"))
    )
    (net (code "42") (name "Net-(R18-P$2)") (class "Default")
      (node (ref "D12") (pin "0") (pinfunction "0_0") (pintype "bidirectional"))
      (node (ref "R18") (pin "1") (pinfunction "P$2_1") (pintype "bidirectional"))
    )
    (net (code "43") (name "Net-(R19-P$2)") (class "Default")
      (node (ref "D11") (pin "0") (pinfunction "0_0") (pintype "bidirectional"))
      (node (ref "R19") (pin "1") (pinfunction "P$2_1") (pintype "bidirectional"))
    )
    (net (code "44") (name "Net-(R20-P$2)") (class "Default")
      (node (ref "D10") (pin "0") (pinfunction "0_0") (pintype "bidirectional"))
      (node (ref "R20") (pin "1") (pinfunction "P$2_1") (pintype "bidirectional"))
    )
    (net (code "45") (name "Net-(R21-P$1)") (class "Default")
      (node (ref "R21") (pin "0") (pinfunction "P$1_0") (pintype "bidirectional"))
      (node (ref "U1") (pin "P$25") (pinfunction "PIO2_10_P$25") (pintype "bidirectional"))
    )
    (net (code "46") (name "Net-(R21-P$2)") (class "Default")
      (node (ref "D3") (pin "0") (pinfunction "0_0") (pintype "bidirectional"))
      (node (ref "R21") (pin "1") (pinfunction "P$2_1") (pintype "bidirectional"))
    )
    (net (code "47") (name "Net-(R22-P$1)") (class "Default")
      (node (ref "D2") (pin "0") (pinfunction "0_0") (pintype "bidirectional"))
      (node (ref "R22") (pin "0") (pinfunction "P$1_0") (pintype "bidirectional"))
    )
    (net (code "48") (name "Net-(R23-P$2)") (class "Default")
      (node (ref "R23") (pin "1") (pinfunction "P$2_1") (pintype "bidirectional"))
      (node (ref "U$1") (pin "P$2") (pinfunction "P$2_P$2") (pintype "bidirectional"))
    )
    (net (code "49") (name "Net-(R24-P$2)") (class "Default")
      (node (ref "R24") (pin "1") (pinfunction "P$2_1") (pintype "bidirectional"))
      (node (ref "U$1") (pin "P$5") (pinfunction "P$5_P$5") (pintype "bidirectional"))
    )
    (net (code "50") (name "Net-(R25-P$2)") (class "Default")
      (node (ref "R25") (pin "1") (pinfunction "P$2_1") (pintype "bidirectional"))
      (node (ref "U$1") (pin "P$8") (pinfunction "P$8_P$8") (pintype "bidirectional"))
    )
    (net (code "51") (name "Net-(R29-P$2)") (class "Default")
      (node (ref "D9") (pin "0") (pinfunction "0_0") (pintype "bidirectional"))
      (node (ref "R29") (pin "1") (pinfunction "P$2_1") (pintype "bidirectional"))
    )
    (net (code "52") (name "Net-(R30-P$2)") (class "Default")
      (node (ref "D8") (pin "0") (pinfunction "0_0") (pintype "bidirectional"))
      (node (ref "R30") (pin "1") (pinfunction "P$2_1") (pintype "bidirectional"))
    )
    (net (code "53") (name "Net-(R31-P$2)") (class "Default")
      (node (ref "D7") (pin "0") (pinfunction "0_0") (pintype "bidirectional"))
      (node (ref "R31") (pin "1") (pinfunction "P$2_1") (pintype "bidirectional"))
    )
    (net (code "54") (name "Net-(R32-P$2)") (class "Default")
      (node (ref "D6") (pin "0") (pinfunction "0_0") (pintype "bidirectional"))
      (node (ref "R32") (pin "1") (pinfunction "P$2_1") (pintype "bidirectional"))
    )
    (net (code "55") (name "Net-(R33-P$2)") (class "Default")
      (node (ref "D5") (pin "0") (pinfunction "0_0") (pintype "bidirectional"))
      (node (ref "R33") (pin "1") (pinfunction "P$2_1") (pintype "bidirectional"))
    )
    (net (code "56") (name "Net-(R34-P$2)") (class "Default")
      (node (ref "D4") (pin "0") (pinfunction "0_0") (pintype "bidirectional"))
      (node (ref "R34") (pin "1") (pinfunction "P$2_1") (pintype "bidirectional"))
    )
    (net (code "57") (name "Net-(R35-P$1)") (class "Default")
      (node (ref "R35") (pin "0") (pinfunction "P$1_0") (pintype "bidirectional"))
      (node (ref "U1") (pin "P$14") (pinfunction "PIO0_3_P$14") (pintype "bidirectional"))
    )
    (net (code "58") (name "Net-(R40-P$2)") (class "Default")
      (node (ref "D22") (pin "0") (pinfunction "0_0") (pintype "bidirectional"))
      (node (ref "R40") (pin "1") (pinfunction "P$2_1") (pintype "bidirectional"))
    )
    (net (code "59") (name "Net-(R41-P$2)") (class "Default")
      (node (ref "D21") (pin "0") (pinfunction "0_0") (pintype "bidirectional"))
      (node (ref "R41") (pin "1") (pinfunction "P$2_1") (pintype "bidirectional"))
    )
    (net (code "60") (name "unconnected-(J3-+3V3-PadP$5)") (class "Default")
      (node (ref "J3") (pin "P$5") (pinfunction "+3V3_P$5") (pintype "bidirectional"))
    )
    (net (code "61") (name "unconnected-(U$1-PadP$10)") (class "Default")
      (node (ref "U$1") (pin "P$10") (pinfunction "P$10_P$10") (pintype "bidirectional"))
    )
    (net (code "62") (name "unconnected-(U1-PIO0_2{slash}SSEL0{slash}CT16B0_CAP0-PadP$10)") (class "Default")
      (node (ref "U1") (pin "P$10") (pinfunction "PIO0_2/SSEL0/CT16B0_CAP0_P$10") (pintype "bidirectional"))
    )
    (net (code "63") (name "unconnected-(U1-PIO0_4{slash}SCL-PadP$15)") (class "Default")
      (node (ref "U1") (pin "P$15") (pinfunction "PIO0_4/SCL_P$15") (pintype "bidirectional"))
    )
    (net (code "64") (name "unconnected-(U1-PIO0_5{slash}SDA-PadP$16)") (class "Default")
      (node (ref "U1") (pin "P$16") (pinfunction "PIO0_5/SDA_P$16") (pintype "bidirectional"))
    )
    (net (code "65") (name "unconnected-(U1-PIO0_6{slash}SCK0-PadP$23)") (class "Default")
      (node (ref "U1") (pin "P$23") (pinfunction "PIO0_6/SCK0_P$23") (pintype "bidirectional"))
    )
    (net (code "66") (name "unconnected-(U1-PIO0_8{slash}MISO0{slash}CT16B0_MAT0-PadP$27)") (class "Default")
      (node (ref "U1") (pin "P$27") (pinfunction "PIO0_8/MISO0/CT16B0_MAT0_P$27") (pintype "bidirectional"))
    )
    (net (code "67") (name "unconnected-(U1-PIO0_9{slash}MOSI0{slash}CT16B0_MAT1-PadP$28)") (class "Default")
      (node (ref "U1") (pin "P$28") (pinfunction "PIO0_9/MOSI0/CT16B0_MAT1_P$28") (pintype "bidirectional"))
    )
    (net (code "68") (name "unconnected-(U1-PIO1_4{slash}AD5{slash}CT32B1_MAT3{slash}WAKEUP-PadP$40)") (class "Default")
      (node (ref "U1") (pin "P$40") (pinfunction "PIO1_4/AD5/CT32B1_MAT3/WAKEUP_P$40") (pintype "bidirectional"))
    )
    (net (code "69") (name "unconnected-(U1-PIO1_8{slash}CT16B1_CAP0-PadP$9)") (class "Default")
      (node (ref "U1") (pin "P$9") (pinfunction "PIO1_8/CT16B1_CAP0_P$9") (pintype "bidirectional"))
    )
    (net (code "70") (name "unconnected-(U1-PIO1_10{slash}AD6{slash}CT16B1_MAT1-PadP$30)") (class "Default")
      (node (ref "U1") (pin "P$30") (pinfunction "PIO1_10/AD6/CT16B1_MAT1_P$30") (pintype "bidirectional"))
    )
    (net (code "71") (name "unconnected-(U1-PIO1_11{slash}AD7-PadP$42)") (class "Default")
      (node (ref "U1") (pin "P$42") (pinfunction "PIO1_11/AD7_P$42") (pintype "bidirectional"))
    )
    (net (code "72") (name "unconnected-(U1-PIO2_1{slash}DSR{slash}SCK1-PadP$13)") (class "Default")
      (node (ref "U1") (pin "P$13") (pinfunction "PIO2_1/DSR/SCK1_P$13") (pintype "bidirectional"))
    )
    (net (code "73") (name "unconnected-(U1-PIO2_2{slash}DCD{slash}MISO1-PadP$26)") (class "Default")
      (node (ref "U1") (pin "P$26") (pinfunction "PIO2_2/DCD/MISO1_P$26") (pintype "bidirectional"))
    )
    (net (code "74") (name "unconnected-(U1-PIO2_6-PadP$1)") (class "Default")
      (node (ref "U1") (pin "P$1") (pinfunction "PIO2_6_P$1") (pintype "bidirectional"))
    )
    (net (code "75") (name "unconnected-(U1-PIO2_7-PadP$11)") (class "Default")
      (node (ref "U1") (pin "P$11") (pinfunction "PIO2_7_P$11") (pintype "bidirectional"))
    )
    (net (code "76") (name "unconnected-(U1-PIO2_11{slash}SCK0-PadP$31)") (class "Default")
      (node (ref "U1") (pin "P$31") (pinfunction "PIO2_11/SCK0_P$31") (pintype "bidirectional"))
    )
    (net (code "77") (name "unconnected-(U1-PIO3_0{slash}DTR-PadP$36)") (class "Default")
      (node (ref "U1") (pin "P$36") (pinfunction "PIO3_0/DTR_P$36") (pintype "bidirectional"))
    )
    (net (code "78") (name "unconnected-(U1-PIO3_2{slash}DCD-PadP$43)") (class "Default")
      (node (ref "U1") (pin "P$43") (pinfunction "PIO3_2/DCD_P$43") (pintype "bidirectional"))
    )
    (net (code "79") (name "unconnected-(U1-SWCLK{slash}PIO0_10{slash}SCK0{slash}CT16B0_MAT2-PadP$29)") (class "Default")
      (node (ref "U1") (pin "P$29") (pinfunction "SWCLK/PIO0_10/SCK0/CT16B0_MAT2_P$29") (pintype "bidirectional"))
    )
    (net (code "80") (name "unconnected-(U1-SWDIO{slash}PIO1_3{slash}AD4{slash}CT32B1_MAT2-PadP$39)") (class "Default")
      (node (ref "U1") (pin "P$39") (pinfunction "SWDIO/PIO1_3/AD4/CT32B1_MAT2_P$39") (pintype "bidirectional"))
    )
    (net (code "81") (name "unconnected-(VR1-ON{slash}OFF-PadP$5)") (class "Default")
      (node (ref "VR1") (pin "P$5") (pinfunction "ON/OFF_P$5") (pintype "bidirectional"))
    )
    (net (code "82") (name "unconnected-(VR1-SS-PadP$2)") (class "Default")
      (node (ref "VR1") (pin "P$2") (pinfunction "SS_P$2") (pintype "bidirectional"))
    )
    (net (code "83") (name "unconnected-(VR1-SYNC-PadP$3)") (class "Default")
      (node (ref "VR1") (pin "P$3") (pinfunction "SYNC_P$3") (pintype "bidirectional"))
    )
  )
)
